# DB10012_ControlController.net
KiCad netlist of a schematic drawn in Altium Designer
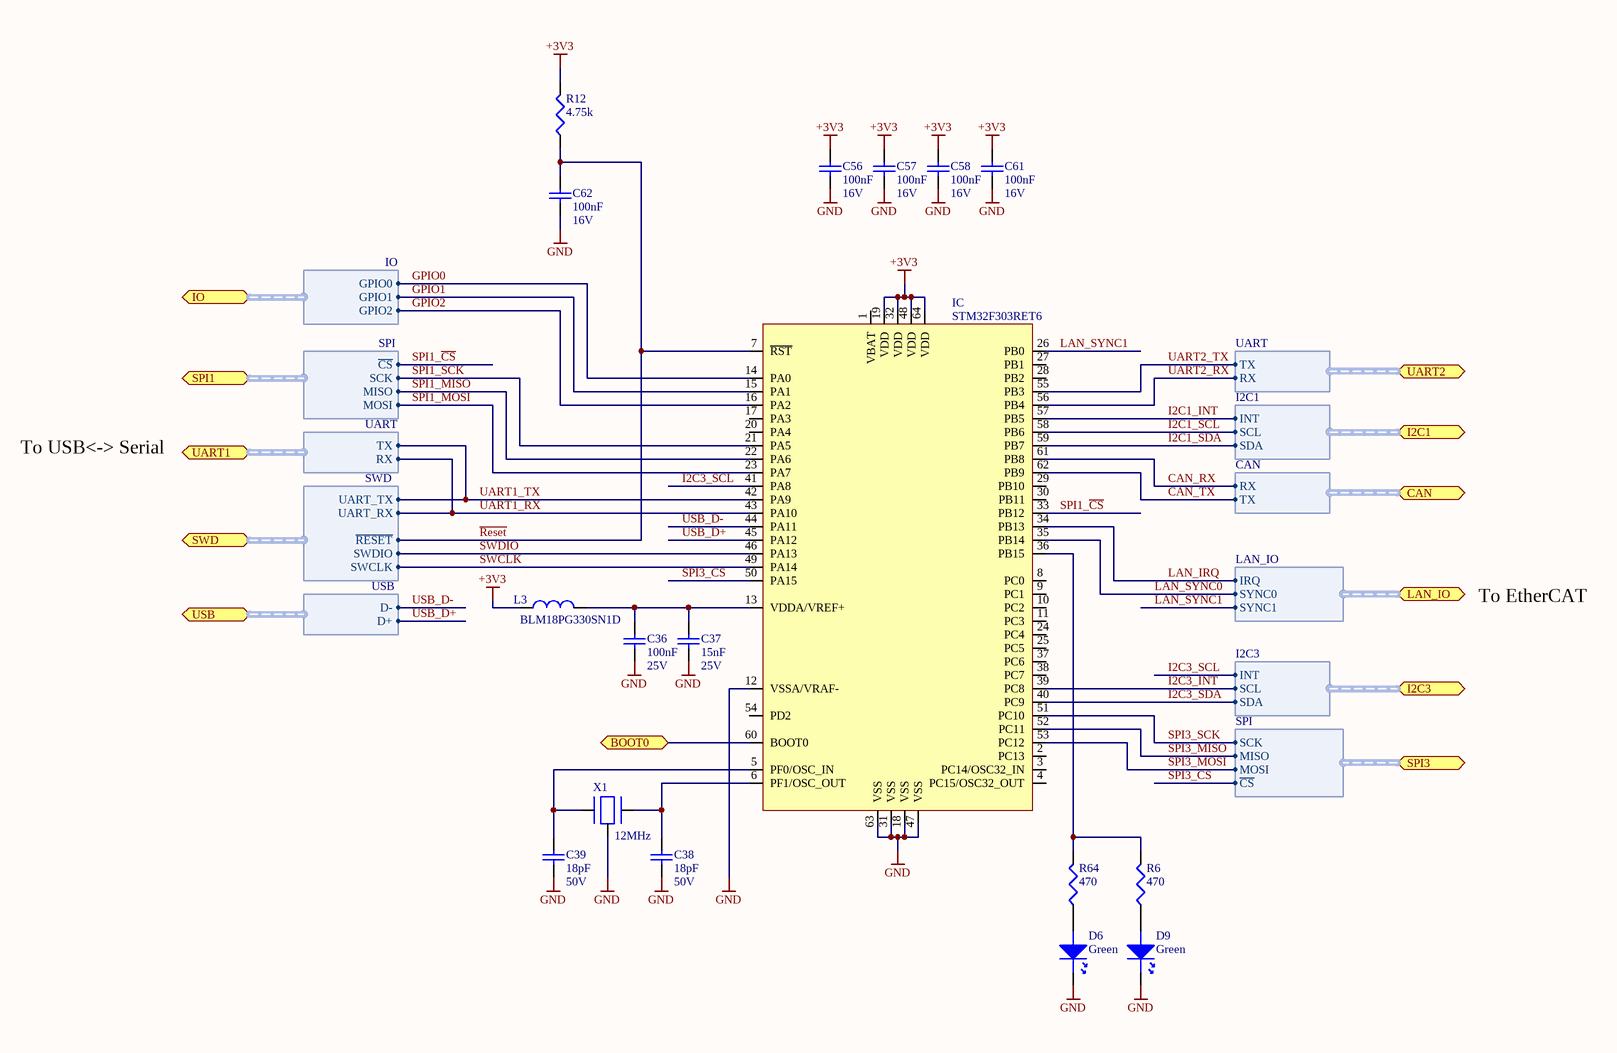
[diagram p0: DB10012_ControlController.SchDoc]

(export (version "E")
  (design (tool "Eeschema 10.0.6"))
  (components
    (comp (ref "C36")
      (value "100nF")
      (footprint "C0402")
      (description "Capacitor, 100nF, 25V, X7R")
      (fields (field (name "VOLTAGE RATING") "25V"))
      (libsource (lib "AR_Capacitors_Ceramic") (part "100nF/0402/CER/25V"))
    )
    (comp (ref "C37")
      (value "15nF")
      (footprint "C0402")
      (description "Capacitor, 15nF, 25V, X7R")
      (fields (field (name "VOLTAGE RATING") "25V"))
      (libsource (lib "AR_Capacitors_Ceramic") (part "15nF/0402/CER/25V"))
    )
    (comp (ref "C38")
      (value "18pF")
      (footprint "C0402")
      (description "Capacitor, 18pF, 50V, NP0")
      (fields (field (name "VOLTAGE RATING") "50V"))
      (libsource (lib "AR_Capacitors_Ceramic") (part "18pF/0402/CER/50V"))
    )
    (comp (ref "C39")
      (value "18pF")
      (footprint "C0402")
      (description "Capacitor, 18pF, 50V, NP0")
      (fields (field (name "VOLTAGE RATING") "50V"))
      (libsource (lib "AR_Capacitors_Ceramic") (part "18pF/0402/CER/50V"))
    )
    (comp (ref "C56")
      (value "100nF")
      (footprint "C0402")
      (description "Capacitor, 100nF, 16V, X7R")
      (fields (field (name "VOLTAGE RATING") "16V"))
      (libsource (lib "AR_Capacitors_Ceramic") (part "100nF/0402/CER/16V"))
    )
    (comp (ref "C57")
      (value "100nF")
      (footprint "C0402")
      (description "Capacitor, 100nF, 16V, X7R")
      (fields (field (name "VOLTAGE RATING") "16V"))
      (libsource (lib "AR_Capacitors_Ceramic") (part "100nF/0402/CER/16V"))
    )
    (comp (ref "C58")
      (value "100nF")
      (footprint "C0402")
      (description "Capacitor, 100nF, 16V, X7R")
      (fields (field (name "VOLTAGE RATING") "16V"))
      (libsource (lib "AR_Capacitors_Ceramic") (part "100nF/0402/CER/16V"))
    )
    (comp (ref "C61")
      (value "100nF")
      (footprint "C0402")
      (description "Capacitor, 100nF, 16V, X7R")
      (fields (field (name "VOLTAGE RATING") "16V"))
      (libsource (lib "AR_Capacitors_Ceramic") (part "100nF/0402/CER/16V"))
    )
    (comp (ref "C62")
      (value "100nF")
      (footprint "C0402")
      (description "Capacitor, 100nF, 16V, X7R")
      (fields (field (name "VOLTAGE RATING") "16V"))
      (libsource (lib "AR_Capacitors_Ceramic") (part "100nF/0402/CER/16V"))
    )
    (comp (ref "D6")
      (value "Green")
      (footprint "D-0805")
      (description "Led, Green, Li:12mcd, Vf:2.2V, If:0.02A")
      (libsource (lib "AR_Misc") (part "KP-2012SGC"))
    )
    (comp (ref "D9")
      (value "Green")
      (footprint "D-0805")
      (description "Led, Green, Li:12mcd, Vf:2.2V, If:0.02A")
      (libsource (lib "AR_Misc") (part "KP-2012SGC"))
    )
    (comp (ref "IC")
      (value "STM32F303RET6")
      (footprint "LQFP64")
      (description "ARM Cortex-M4, 72 MHz, 512 KB, 64 KB, 64")
      (libsource (lib "AR_Microcontrollers") (part "STM32F303RET6"))
    )
    (comp (ref "L3")
      (value "BLM18PG330SN1D")
      (footprint "L0603")
      (description "Ferrite Bead, Impedance:33ohm, DC Resistance Max:0.025ohm, DC Current Rating:3A")
      (libsource (lib "AR_Inductors") (part "BLM18PG330SN1D"))
    )
    (comp (ref "R6")
      (value "470")
      (footprint "0402")
      (description "Resistor, 470, 1%, 0.0625W, 50V, 100PPM, 0402")
      (libsource (lib "AR_Resistors_SMD") (part "470/0402/0063W/50V"))
    )
    (comp (ref "R12")
      (value "4.75k")
      (footprint "0402")
      (description "Resistor, 4.75k, 0.1%, 0.0625W, 50V, 100PPM, 0402")
      (libsource (lib "AR_Resistors_SMD") (part "4.75k/0402/0063W/50V"))
    )
    (comp (ref "R64")
      (value "470")
      (footprint "0402")
      (description "Resistor, 470, 1%, 0.0625W, 50V, 100PPM, 0402")
      (libsource (lib "AR_Resistors_SMD") (part "470/0402/0063W/50V"))
    )
    (comp (ref "X1")
      (value "12MHz")
      (footprint "7M")
      (description "CRYSTAL, 12MHz,18PF CL, 3.2X2.5MM SMT")
      (libsource (lib "AR_Crystals") (part "7M-12.000MAAJ-T"))
    )
  )
  (nets
    (net (code "10") (name "+3V3") (class "Default")
      (node (ref "C56") (pin "2") (pinfunction "2_2") (pintype "passive"))
      (node (ref "C57") (pin "2") (pinfunction "2_2") (pintype "passive"))
      (node (ref "C58") (pin "2") (pinfunction "2_2") (pintype "passive"))
      (node (ref "C61") (pin "2") (pinfunction "2_2") (pintype "passive"))
      (node (ref "IC") (pin "19") (pinfunction "VDD_19") (pintype "passive"))
      (node (ref "IC") (pin "32") (pinfunction "VDD_32") (pintype "passive"))
      (node (ref "IC") (pin "48") (pinfunction "VDD_48") (pintype "passive"))
      (node (ref "IC") (pin "64") (pinfunction "VDD_64") (pintype "passive"))
      (node (ref "L3") (pin "2") (pinfunction "2_2") (pintype "passive"))
      (node (ref "R12") (pin "2") (pinfunction "2_2") (pintype "passive"))
    )
    (net (code "11") (name "/BOOT0") (class "Default")
      (node (ref "IC") (pin "60") (pinfunction "BOOT0_60") (pintype "passive"))
    )
    (net (code "12") (name "/CAN_RX") (class "Default")
      (node (ref "IC") (pin "61") (pinfunction "PB8_61") (pintype "passive"))
    )
    (net (code "13") (name "/CAN_TX") (class "Default")
      (node (ref "IC") (pin "62") (pinfunction "PB9_62") (pintype "passive"))
    )
    (net (code "14") (name "/GPIO0") (class "Default")
      (node (ref "IC") (pin "14") (pinfunction "PA0_14") (pintype "passive"))
    )
    (net (code "15") (name "/GPIO1") (class "Default")
      (node (ref "IC") (pin "15") (pinfunction "PA1_15") (pintype "passive"))
    )
    (net (code "16") (name "/GPIO2") (class "Default")
      (node (ref "IC") (pin "16") (pinfunction "PA2_16") (pintype "passive"))
    )
    (net (code "17") (name "/I2C1_INT") (class "Default")
      (node (ref "IC") (pin "57") (pinfunction "PB5_57") (pintype "passive"))
    )
    (net (code "18") (name "/I2C1_SCL") (class "Default")
      (node (ref "IC") (pin "58") (pinfunction "PB6_58") (pintype "passive"))
    )
    (net (code "19") (name "/I2C1_SDA") (class "Default")
      (node (ref "IC") (pin "59") (pinfunction "PB7_59") (pintype "passive"))
    )
    (net (code "20") (name "/I2C3_INT") (class "Default")
      (node (ref "IC") (pin "39") (pinfunction "PC8_39") (pintype "passive"))
    )
    (net (code "21") (name "/I2C3_SCL") (class "Default")
      (node (ref "IC") (pin "41") (pinfunction "PA8_41") (pintype "passive"))
    )
    (net (code "22") (name "/I2C3_SDA") (class "Default")
      (node (ref "IC") (pin "40") (pinfunction "PC9_40") (pintype "passive"))
    )
    (net (code "23") (name "/LAN_IRQ") (class "Default")
      (node (ref "IC") (pin "34") (pinfunction "PB13_34") (pintype "passive"))
    )
    (net (code "24") (name "/LAN_SYNC0") (class "Default")
      (node (ref "IC") (pin "35") (pinfunction "PB14_35") (pintype "passive"))
    )
    (net (code "25") (name "/LAN_SYNC1") (class "Default")
      (node (ref "IC") (pin "26") (pinfunction "PB0_26") (pintype "passive"))
    )
    (net (code "26") (name "/SPI1_MISO") (class "Default")
      (node (ref "IC") (pin "22") (pinfunction "PA6_22") (pintype "passive"))
    )
    (net (code "27") (name "/SPI1_MOSI") (class "Default")
      (node (ref "IC") (pin "23") (pinfunction "PA7_23") (pintype "passive"))
    )
    (net (code "28") (name "/SPI1_SCK") (class "Default")
      (node (ref "IC") (pin "21") (pinfunction "PA5_21") (pintype "passive"))
    )
    (net (code "29") (name "/SPI1_~{CS}") (class "Default")
      (node (ref "IC") (pin "33") (pinfunction "PB12_33") (pintype "passive"))
    )
    (net (code "30") (name "/SPI3_MISO") (class "Default")
      (node (ref "IC") (pin "52") (pinfunction "PC11_52") (pintype "passive"))
    )
    (net (code "31") (name "/SPI3_MOSI") (class "Default")
      (node (ref "IC") (pin "53") (pinfunction "PC12_53") (pintype "passive"))
    )
    (net (code "32") (name "/SPI3_SCK") (class "Default")
      (node (ref "IC") (pin "51") (pinfunction "PC10_51") (pintype "passive"))
    )
    (net (code "33") (name "/SPI3_~{CS}") (class "Default")
      (node (ref "IC") (pin "50") (pinfunction "PA15_50") (pintype "passive"))
    )
    (net (code "34") (name "/SWCLK") (class "Default")
      (node (ref "IC") (pin "49") (pinfunction "PA14_49") (pintype "passive"))
    )
    (net (code "35") (name "/SWDIO") (class "Default")
      (node (ref "IC") (pin "46") (pinfunction "PA13_46") (pintype "passive"))
    )
    (net (code "36") (name "/UART1_RX") (class "Default")
      (node (ref "IC") (pin "43") (pinfunction "PA10_43") (pintype "passive"))
    )
    (net (code "37") (name "/UART1_TX") (class "Default")
      (node (ref "IC") (pin "42") (pinfunction "PA9_42") (pintype "passive"))
    )
    (net (code "38") (name "/UART2_RX") (class "Default")
      (node (ref "IC") (pin "56") (pinfunction "PB4_56") (pintype "passive"))
    )
    (net (code "39") (name "/UART2_TX") (class "Default")
      (node (ref "IC") (pin "55") (pinfunction "PB3_55") (pintype "passive"))
    )
    (net (code "40") (name "/USB_D+") (class "Default")
      (node (ref "IC") (pin "45") (pinfunction "PA12_45") (pintype "passive"))
    )
    (net (code "41") (name "/USB_D-") (class "Default")
      (node (ref "IC") (pin "44") (pinfunction "PA11_44") (pintype "passive"))
    )
    (net (code "51") (name "/~{Reset}") (class "Default")
      (node (ref "C62") (pin "2") (pinfunction "2_2") (pintype "passive"))
      (node (ref "IC") (pin "7") (pinfunction "~{RST}_7") (pintype "passive"))
      (node (ref "R12") (pin "1") (pinfunction "1_1") (pintype "passive"))
    )
    (net (code "52") (name "GND") (class "Default")
      (node (ref "C36") (pin "1") (pinfunction "1_1") (pintype "passive"))
      (node (ref "C37") (pin "1") (pinfunction "1_1") (pintype "passive"))
      (node (ref "C38") (pin "1") (pinfunction "1_1") (pintype "passive"))
      (node (ref "C39") (pin "1") (pinfunction "1_1") (pintype "passive"))
      (node (ref "C56") (pin "1") (pinfunction "1_1") (pintype "passive"))
      (node (ref "C57") (pin "1") (pinfunction "1_1") (pintype "passive"))
      (node (ref "C58") (pin "1") (pinfunction "1_1") (pintype "passive"))
      (node (ref "C61") (pin "1") (pinfunction "1_1") (pintype "passive"))
      (node (ref "C62") (pin "1") (pinfunction "1_1") (pintype "passive"))
      (node (ref "D6") (pin "K") (pinfunction "K_K") (pintype "passive"))
      (node (ref "D9") (pin "K") (pinfunction "K_K") (pintype "passive"))
      (node (ref "IC") (pin "12") (pinfunction "VSSA/VRAF-_12") (pintype "passive"))
      (node (ref "IC") (pin "18") (pinfunction "VSS_18") (pintype "passive"))
      (node (ref "IC") (pin "31") (pinfunction "VSS_31") (pintype "passive"))
      (node (ref "IC") (pin "47") (pinfunction "VSS_47") (pintype "passive"))
      (node (ref "IC") (pin "63") (pinfunction "VSS_63") (pintype "passive"))
      (node (ref "X1") (pin "0") (pinfunction "0_0") (pintype "power_in"))
    )
    (net (code "53") (name "Net-(D6-PadA)") (class "Default")
      (node (ref "D6") (pin "A") (pinfunction "A_A") (pintype "passive"))
      (node (ref "R64") (pin "1") (pinfunction "1_1") (pintype "passive"))
    )
    (net (code "54") (name "Net-(D9-PadA)") (class "Default")
      (node (ref "D9") (pin "A") (pinfunction "A_A") (pintype "passive"))
      (node (ref "R6") (pin "1") (pinfunction "1_1") (pintype "passive"))
    )
    (net (code "55") (name "Net-(IC-PB15)") (class "Default")
      (node (ref "IC") (pin "36") (pinfunction "PB15_36") (pintype "passive"))
      (node (ref "R6") (pin "2") (pinfunction "2_2") (pintype "passive"))
      (node (ref "R64") (pin "2") (pinfunction "2_2") (pintype "passive"))
    )
    (net (code "56") (name "Net-(IC-PF0{slash}OSC_IN)") (class "Default")
      (node (ref "C39") (pin "2") (pinfunction "2_2") (pintype "passive"))
      (node (ref "IC") (pin "5") (pinfunction "PF0/OSC_IN_5") (pintype "passive"))
      (node (ref "X1") (pin "2") (pinfunction "2_2") (pintype "passive"))
    )
    (net (code "57") (name "Net-(IC-PF1{slash}OSC_OUT)") (class "Default")
      (node (ref "C38") (pin "2") (pinfunction "2_2") (pintype "passive"))
      (node (ref "IC") (pin "6") (pinfunction "PF1/OSC_OUT_6") (pintype "passive"))
      (node (ref "X1") (pin "1") (pinfunction "1_1") (pintype "passive"))
    )
    (net (code "58") (name "Net-(IC-VDDA{slash}VREF+)") (class "Default")
      (node (ref "C36") (pin "2") (pinfunction "2_2") (pintype "passive"))
      (node (ref "C37") (pin "2") (pinfunction "2_2") (pintype "passive"))
      (node (ref "IC") (pin "13") (pinfunction "VDDA/VREF+_13") (pintype "passive"))
      (node (ref "L3") (pin "1") (pinfunction "1_1") (pintype "passive"))
    )
    (net (code "59") (name "unconnected-(IC-PA3-Pad17)") (class "Default")
      (node (ref "IC") (pin "17") (pinfunction "PA3_17") (pintype "passive"))
    )
    (net (code "60") (name "unconnected-(IC-PA4-Pad20)") (class "Default")
      (node (ref "IC") (pin "20") (pinfunction "PA4_20") (pintype "passive"))
    )
    (net (code "61") (name "unconnected-(IC-PB1-Pad27)") (class "Default")
      (node (ref "IC") (pin "27") (pinfunction "PB1_27") (pintype "passive"))
    )
    (net (code "62") (name "unconnected-(IC-PB2-Pad28)") (class "Default")
      (node (ref "IC") (pin "28") (pinfunction "PB2_28") (pintype "passive"))
    )
    (net (code "63") (name "unconnected-(IC-PB10-Pad29)") (class "Default")
      (node (ref "IC") (pin "29") (pinfunction "PB10_29") (pintype "passive"))
    )
    (net (code "64") (name "unconnected-(IC-PB11-Pad30)") (class "Default")
      (node (ref "IC") (pin "30") (pinfunction "PB11_30") (pintype "passive"))
    )
    (net (code "65") (name "unconnected-(IC-PC0-Pad8)") (class "Default")
      (node (ref "IC") (pin "8") (pinfunction "PC0_8") (pintype "passive"))
    )
    (net (code "66") (name "unconnected-(IC-PC1-Pad9)") (class "Default")
      (node (ref "IC") (pin "9") (pinfunction "PC1_9") (pintype "passive"))
    )
    (net (code "67") (name "unconnected-(IC-PC2-Pad10)") (class "Default")
      (node (ref "IC") (pin "10") (pinfunction "PC2_10") (pintype "passive"))
    )
    (net (code "68") (name "unconnected-(IC-PC3-Pad11)") (class "Default")
      (node (ref "IC") (pin "11") (pinfunction "PC3_11") (pintype "passive"))
    )
    (net (code "69") (name "unconnected-(IC-PC4-Pad24)") (class "Default")
      (node (ref "IC") (pin "24") (pinfunction "PC4_24") (pintype "passive"))
    )
    (net (code "70") (name "unconnected-(IC-PC5-Pad25)") (class "Default")
      (node (ref "IC") (pin "25") (pinfunction "PC5_25") (pintype "passive"))
    )
    (net (code "71") (name "unconnected-(IC-PC6-Pad37)") (class "Default")
      (node (ref "IC") (pin "37") (pinfunction "PC6_37") (pintype "passive"))
    )
    (net (code "72") (name "unconnected-(IC-PC7-Pad38)") (class "Default")
      (node (ref "IC") (pin "38") (pinfunction "PC7_38") (pintype "passive"))
    )
    (net (code "73") (name "unconnected-(IC-PC13-Pad2)") (class "Default")
      (node (ref "IC") (pin "2") (pinfunction "PC13_2") (pintype "passive"))
    )
    (net (code "74") (name "unconnected-(IC-PC14{slash}OSC32_IN-Pad3)") (class "Default")
      (node (ref "IC") (pin "3") (pinfunction "PC14/OSC32_IN_3") (pintype "passive"))
    )
    (net (code "75") (name "unconnected-(IC-PC15{slash}OSC32_OUT-Pad4)") (class "Default")
      (node (ref "IC") (pin "4") (pinfunction "PC15/OSC32_OUT_4") (pintype "passive"))
    )
    (net (code "76") (name "unconnected-(IC-PD2-Pad54)") (class "Default")
      (node (ref "IC") (pin "54") (pinfunction "PD2_54") (pintype "passive"))
    )
    (net (code "77") (name "unconnected-(IC-VBAT-Pad1)") (class "Default")
      (node (ref "IC") (pin "1") (pinfunction "VBAT_1") (pintype "passive"))
    )
  )
)
